# i-oboard_2.net
KiCad netlist of a schematic drawn in EAGLE
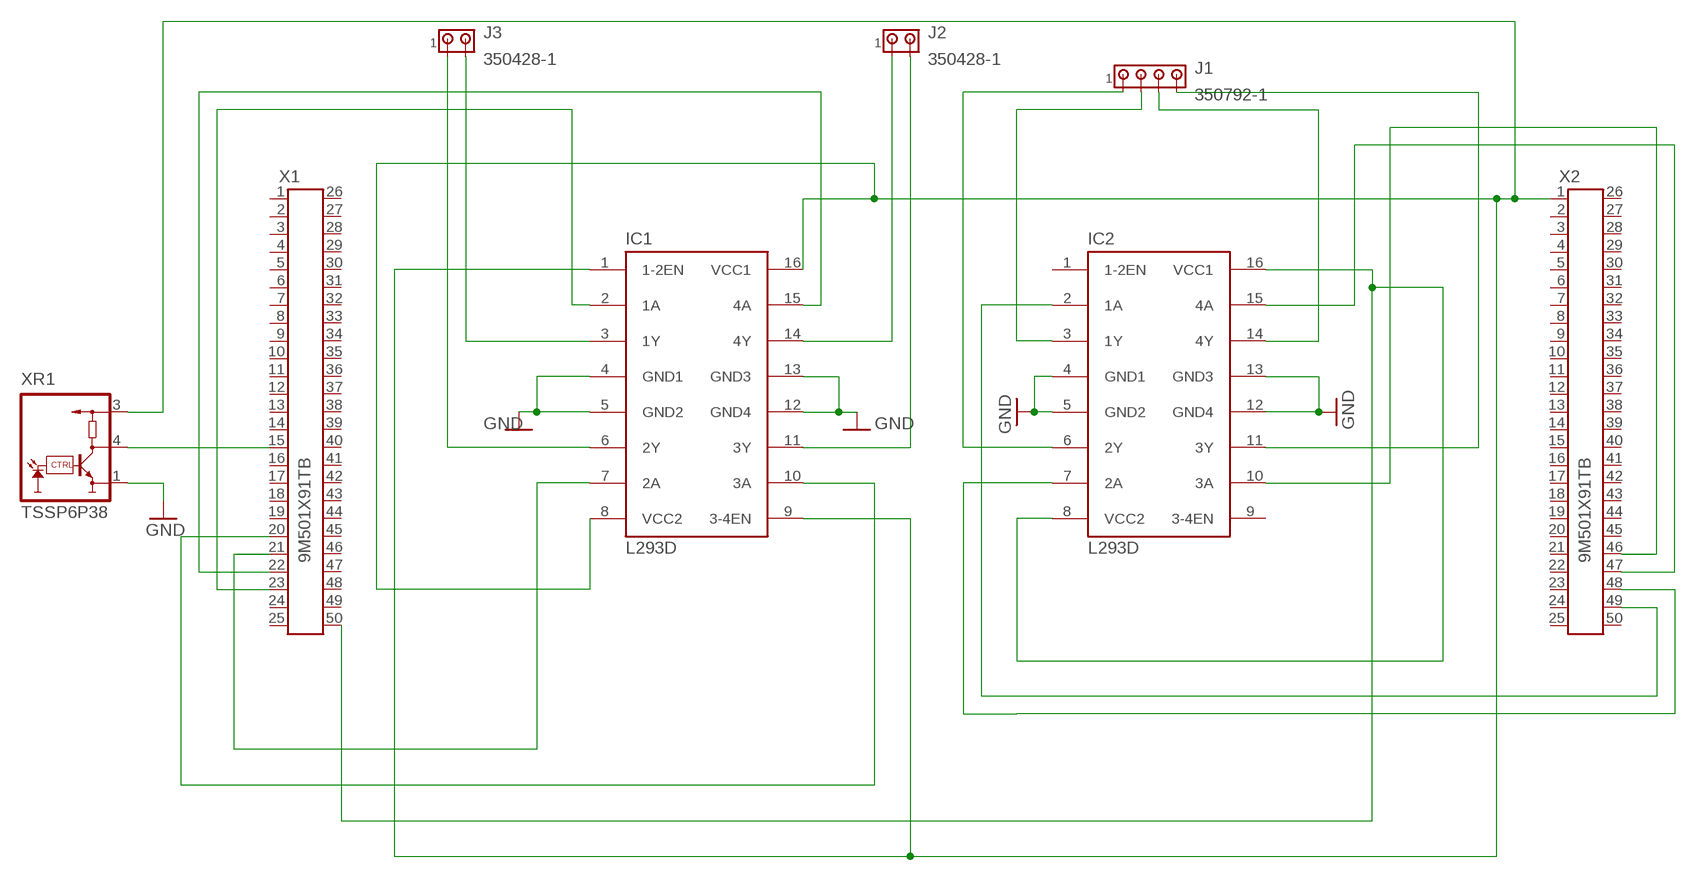
[diagram p0: schematic, sheet 1]

(export (version "E")
  (design (tool "Eeschema 10.0.6"))
  (components
    (comp (ref "IC1")
      (value "L293D")
      (footprint "eagle-import:DIL16")
      (libsource (lib "eagle-import") (part "L293D"))
    )
    (comp (ref "IC2")
      (value "L293D")
      (footprint "eagle-import:DIL16")
      (libsource (lib "eagle-import") (part "L293D"))
    )
    (comp (ref "J1")
      (value "350792-1")
      (footprint "eagle-import:350792-1")
      (libsource (lib "eagle-import") (part "350792-1"))
    )
    (comp (ref "J2")
      (value "350428-1")
      (footprint "eagle-import:350428-1")
      (libsource (lib "eagle-import") (part "350428-1"))
    )
    (comp (ref "J3")
      (value "350428-1")
      (footprint "eagle-import:350428-1")
      (libsource (lib "eagle-import") (part "350428-1"))
    )
    (comp (ref "X1")
      (value "9M501X91TB")
      (footprint "eagle-import:9M501X91")
      (libsource (lib "eagle-import") (part "9M501X91TB"))
    )
    (comp (ref "X2")
      (value "9M501X91TB")
      (footprint "eagle-import:9M501X91")
      (libsource (lib "eagle-import") (part "9M501X91TB"))
    )
    (comp (ref "XR1")
      (value "TSSP6P38")
      (footprint "eagle-import:TSSP6P38")
      (libsource (lib "eagle-import") (part "TSSP6P38"))
    )
  )
  (nets
    (net (code "1") (name "GND") (class "Default")
      (node (ref "IC1") (pin "12") (pinfunction "GND4_12") (pintype "power_in"))
      (node (ref "IC1") (pin "13") (pinfunction "GND3_13") (pintype "power_in"))
      (node (ref "IC1") (pin "4") (pinfunction "GND1_4") (pintype "power_in"))
      (node (ref "IC1") (pin "5") (pinfunction "GND2_5") (pintype "power_in"))
      (node (ref "IC2") (pin "12") (pinfunction "GND4_12") (pintype "power_in"))
      (node (ref "IC2") (pin "13") (pinfunction "GND3_13") (pintype "power_in"))
      (node (ref "IC2") (pin "4") (pinfunction "GND1_4") (pintype "power_in"))
      (node (ref "IC2") (pin "5") (pinfunction "GND2_5") (pintype "power_in"))
      (node (ref "XR1") (pin "1") (pinfunction "GND_1") (pintype "power_in"))
    )
    (net (code "2") (name "Net-(IC1-1-2EN)") (class "Default")
      (node (ref "IC1") (pin "1") (pinfunction "1-2EN_1") (pintype "input"))
      (node (ref "IC1") (pin "16") (pinfunction "VCC1_16") (pintype "power_in"))
      (node (ref "IC1") (pin "8") (pinfunction "VCC2_8") (pintype "power_in"))
      (node (ref "IC1") (pin "9") (pinfunction "3-4EN_9") (pintype "input"))
      (node (ref "X2") (pin "1") (pinfunction "1_1") (pintype "passive"))
      (node (ref "XR1") (pin "3") (pinfunction "VS_3") (pintype "power_in"))
    )
    (net (code "3") (name "Net-(IC1-1A)") (class "Default")
      (node (ref "IC1") (pin "2") (pinfunction "1A_2") (pintype "input"))
      (node (ref "X1") (pin "23") (pinfunction "23_23") (pintype "passive"))
    )
    (net (code "4") (name "Net-(IC1-1Y)") (class "Default")
      (node (ref "IC1") (pin "3") (pinfunction "1Y_3") (pintype "output"))
      (node (ref "J3") (pin "2") (pinfunction "2_2") (pintype "passive"))
    )
    (net (code "5") (name "Net-(IC1-2A)") (class "Default")
      (node (ref "IC1") (pin "7") (pinfunction "2A_7") (pintype "input"))
      (node (ref "X1") (pin "21") (pinfunction "21_21") (pintype "passive"))
    )
    (net (code "6") (name "Net-(IC1-2Y)") (class "Default")
      (node (ref "IC1") (pin "6") (pinfunction "2Y_6") (pintype "output"))
      (node (ref "J3") (pin "1") (pinfunction "1_1") (pintype "passive"))
    )
    (net (code "7") (name "Net-(IC1-3A)") (class "Default")
      (node (ref "IC1") (pin "10") (pinfunction "3A_10") (pintype "input"))
      (node (ref "X1") (pin "20") (pinfunction "20_20") (pintype "passive"))
    )
    (net (code "8") (name "Net-(IC1-3Y)") (class "Default")
      (node (ref "IC1") (pin "11") (pinfunction "3Y_11") (pintype "output"))
      (node (ref "J2") (pin "2") (pinfunction "2_2") (pintype "passive"))
    )
    (net (code "9") (name "Net-(IC1-4A)") (class "Default")
      (node (ref "IC1") (pin "15") (pinfunction "4A_15") (pintype "input"))
      (node (ref "X1") (pin "22") (pinfunction "22_22") (pintype "passive"))
    )
    (net (code "10") (name "Net-(IC1-4Y)") (class "Default")
      (node (ref "IC1") (pin "14") (pinfunction "4Y_14") (pintype "output"))
      (node (ref "J2") (pin "1") (pinfunction "1_1") (pintype "passive"))
    )
    (net (code "11") (name "Net-(IC2-1A)") (class "Default")
      (node (ref "IC2") (pin "2") (pinfunction "1A_2") (pintype "input"))
      (node (ref "X2") (pin "49") (pinfunction "49_49") (pintype "passive"))
    )
    (net (code "12") (name "Net-(IC2-1Y)") (class "Default")
      (node (ref "IC2") (pin "3") (pinfunction "1Y_3") (pintype "output"))
      (node (ref "J1") (pin "2") (pinfunction "2_2") (pintype "passive"))
    )
    (net (code "13") (name "Net-(IC2-2A)") (class "Default")
      (node (ref "IC2") (pin "7") (pinfunction "2A_7") (pintype "input"))
      (node (ref "X2") (pin "48") (pinfunction "48_48") (pintype "passive"))
    )
    (net (code "14") (name "Net-(IC2-2Y)") (class "Default")
      (node (ref "IC2") (pin "6") (pinfunction "2Y_6") (pintype "output"))
      (node (ref "J1") (pin "1") (pinfunction "1_1") (pintype "passive"))
    )
    (net (code "15") (name "Net-(IC2-3A)") (class "Default")
      (node (ref "IC2") (pin "10") (pinfunction "3A_10") (pintype "input"))
      (node (ref "X2") (pin "46") (pinfunction "46_46") (pintype "passive"))
    )
    (net (code "16") (name "Net-(IC2-3Y)") (class "Default")
      (node (ref "IC2") (pin "11") (pinfunction "3Y_11") (pintype "output"))
      (node (ref "J1") (pin "4") (pinfunction "4_4") (pintype "passive"))
    )
    (net (code "17") (name "Net-(IC2-4A)") (class "Default")
      (node (ref "IC2") (pin "15") (pinfunction "4A_15") (pintype "input"))
      (node (ref "X2") (pin "47") (pinfunction "47_47") (pintype "passive"))
    )
    (net (code "18") (name "Net-(IC2-4Y)") (class "Default")
      (node (ref "IC2") (pin "14") (pinfunction "4Y_14") (pintype "output"))
      (node (ref "J1") (pin "3") (pinfunction "3_3") (pintype "passive"))
    )
    (net (code "19") (name "Net-(IC2-VCC1)") (class "Default")
      (node (ref "IC2") (pin "16") (pinfunction "VCC1_16") (pintype "power_in"))
      (node (ref "IC2") (pin "8") (pinfunction "VCC2_8") (pintype "power_in"))
      (node (ref "X1") (pin "50") (pinfunction "50_50") (pintype "passive"))
    )
    (net (code "20") (name "Net-(XR1-OUT)") (class "Default")
      (node (ref "X1") (pin "15") (pinfunction "15_15") (pintype "passive"))
      (node (ref "XR1") (pin "4") (pinfunction "OUT_4") (pintype "output"))
    )
    (net (code "21") (name "unconnected-(IC2-1-2EN-Pad1)") (class "Default")
      (node (ref "IC2") (pin "1") (pinfunction "1-2EN_1") (pintype "input"))
    )
    (net (code "22") (name "unconnected-(IC2-3-4EN-Pad9)") (class "Default")
      (node (ref "IC2") (pin "9") (pinfunction "3-4EN_9") (pintype "input"))
    )
    (net (code "23") (name "unconnected-(X1-Pad1)") (class "Default")
      (node (ref "X1") (pin "1") (pinfunction "1_1") (pintype "passive"))
    )
    (net (code "24") (name "unconnected-(X1-Pad2)") (class "Default")
      (node (ref "X1") (pin "2") (pinfunction "2_2") (pintype "passive"))
    )
    (net (code "25") (name "unconnected-(X1-Pad3)") (class "Default")
      (node (ref "X1") (pin "3") (pinfunction "3_3") (pintype "passive"))
    )
    (net (code "26") (name "unconnected-(X1-Pad4)") (class "Default")
      (node (ref "X1") (pin "4") (pinfunction "4_4") (pintype "passive"))
    )
    (net (code "27") (name "unconnected-(X1-Pad5)") (class "Default")
      (node (ref "X1") (pin "5") (pinfunction "5_5") (pintype "passive"))
    )
    (net (code "28") (name "unconnected-(X1-Pad6)") (class "Default")
      (node (ref "X1") (pin "6") (pinfunction "6_6") (pintype "passive"))
    )
    (net (code "29") (name "unconnected-(X1-Pad7)") (class "Default")
      (node (ref "X1") (pin "7") (pinfunction "7_7") (pintype "passive"))
    )
    (net (code "30") (name "unconnected-(X1-Pad8)") (class "Default")
      (node (ref "X1") (pin "8") (pinfunction "8_8") (pintype "passive"))
    )
    (net (code "31") (name "unconnected-(X1-Pad9)") (class "Default")
      (node (ref "X1") (pin "9") (pinfunction "9_9") (pintype "passive"))
    )
    (net (code "32") (name "unconnected-(X1-Pad10)") (class "Default")
      (node (ref "X1") (pin "10") (pinfunction "10_10") (pintype "passive"))
    )
    (net (code "33") (name "unconnected-(X1-Pad11)") (class "Default")
      (node (ref "X1") (pin "11") (pinfunction "11_11") (pintype "passive"))
    )
    (net (code "34") (name "unconnected-(X1-Pad12)") (class "Default")
      (node (ref "X1") (pin "12") (pinfunction "12_12") (pintype "passive"))
    )
    (net (code "35") (name "unconnected-(X1-Pad13)") (class "Default")
      (node (ref "X1") (pin "13") (pinfunction "13_13") (pintype "passive"))
    )
    (net (code "36") (name "unconnected-(X1-Pad14)") (class "Default")
      (node (ref "X1") (pin "14") (pinfunction "14_14") (pintype "passive"))
    )
    (net (code "37") (name "unconnected-(X1-Pad16)") (class "Default")
      (node (ref "X1") (pin "16") (pinfunction "16_16") (pintype "passive"))
    )
    (net (code "38") (name "unconnected-(X1-Pad17)") (class "Default")
      (node (ref "X1") (pin "17") (pinfunction "17_17") (pintype "passive"))
    )
    (net (code "39") (name "unconnected-(X1-Pad18)") (class "Default")
      (node (ref "X1") (pin "18") (pinfunction "18_18") (pintype "passive"))
    )
    (net (code "40") (name "unconnected-(X1-Pad19)") (class "Default")
      (node (ref "X1") (pin "19") (pinfunction "19_19") (pintype "passive"))
    )
    (net (code "41") (name "unconnected-(X1-Pad24)") (class "Default")
      (node (ref "X1") (pin "24") (pinfunction "24_24") (pintype "passive"))
    )
    (net (code "42") (name "unconnected-(X1-Pad25)") (class "Default")
      (node (ref "X1") (pin "25") (pinfunction "25_25") (pintype "passive"))
    )
    (net (code "43") (name "unconnected-(X1-Pad26)") (class "Default")
      (node (ref "X1") (pin "26") (pinfunction "26_26") (pintype "passive"))
    )
    (net (code "44") (name "unconnected-(X1-Pad27)") (class "Default")
      (node (ref "X1") (pin "27") (pinfunction "27_27") (pintype "passive"))
    )
    (net (code "45") (name "unconnected-(X1-Pad28)") (class "Default")
      (node (ref "X1") (pin "28") (pinfunction "28_28") (pintype "passive"))
    )
    (net (code "46") (name "unconnected-(X1-Pad29)") (class "Default")
      (node (ref "X1") (pin "29") (pinfunction "29_29") (pintype "passive"))
    )
    (net (code "47") (name "unconnected-(X1-Pad30)") (class "Default")
      (node (ref "X1") (pin "30") (pinfunction "30_30") (pintype "passive"))
    )
    (net (code "48") (name "unconnected-(X1-Pad31)") (class "Default")
      (node (ref "X1") (pin "31") (pinfunction "31_31") (pintype "passive"))
    )
    (net (code "49") (name "unconnected-(X1-Pad32)") (class "Default")
      (node (ref "X1") (pin "32") (pinfunction "32_32") (pintype "passive"))
    )
    (net (code "50") (name "unconnected-(X1-Pad33)") (class "Default")
      (node (ref "X1") (pin "33") (pinfunction "33_33") (pintype "passive"))
    )
    (net (code "51") (name "unconnected-(X1-Pad34)") (class "Default")
      (node (ref "X1") (pin "34") (pinfunction "34_34") (pintype "passive"))
    )
    (net (code "52") (name "unconnected-(X1-Pad35)") (class "Default")
      (node (ref "X1") (pin "35") (pinfunction "35_35") (pintype "passive"))
    )
    (net (code "53") (name "unconnected-(X1-Pad36)") (class "Default")
      (node (ref "X1") (pin "36") (pinfunction "36_36") (pintype "passive"))
    )
    (net (code "54") (name "unconnected-(X1-Pad37)") (class "Default")
      (node (ref "X1") (pin "37") (pinfunction "37_37") (pintype "passive"))
    )
    (net (code "55") (name "unconnected-(X1-Pad38)") (class "Default")
      (node (ref "X1") (pin "38") (pinfunction "38_38") (pintype "passive"))
    )
    (net (code "56") (name "unconnected-(X1-Pad39)") (class "Default")
      (node (ref "X1") (pin "39") (pinfunction "39_39") (pintype "passive"))
    )
    (net (code "57") (name "unconnected-(X1-Pad40)") (class "Default")
      (node (ref "X1") (pin "40") (pinfunction "40_40") (pintype "passive"))
    )
    (net (code "58") (name "unconnected-(X1-Pad41)") (class "Default")
      (node (ref "X1") (pin "41") (pinfunction "41_41") (pintype "passive"))
    )
    (net (code "59") (name "unconnected-(X1-Pad42)") (class "Default")
      (node (ref "X1") (pin "42") (pinfunction "42_42") (pintype "passive"))
    )
    (net (code "60") (name "unconnected-(X1-Pad43)") (class "Default")
      (node (ref "X1") (pin "43") (pinfunction "43_43") (pintype "passive"))
    )
    (net (code "61") (name "unconnected-(X1-Pad44)") (class "Default")
      (node (ref "X1") (pin "44") (pinfunction "44_44") (pintype "passive"))
    )
    (net (code "62") (name "unconnected-(X1-Pad45)") (class "Default")
      (node (ref "X1") (pin "45") (pinfunction "45_45") (pintype "passive"))
    )
    (net (code "63") (name "unconnected-(X1-Pad46)") (class "Default")
      (node (ref "X1") (pin "46") (pinfunction "46_46") (pintype "passive"))
    )
    (net (code "64") (name "unconnected-(X1-Pad47)") (class "Default")
      (node (ref "X1") (pin "47") (pinfunction "47_47") (pintype "passive"))
    )
    (net (code "65") (name "unconnected-(X1-Pad48)") (class "Default")
      (node (ref "X1") (pin "48") (pinfunction "48_48") (pintype "passive"))
    )
    (net (code "66") (name "unconnected-(X1-Pad49)") (class "Default")
      (node (ref "X1") (pin "49") (pinfunction "49_49") (pintype "passive"))
    )
    (net (code "67") (name "unconnected-(X2-Pad2)") (class "Default")
      (node (ref "X2") (pin "2") (pinfunction "2_2") (pintype "passive"))
    )
    (net (code "68") (name "unconnected-(X2-Pad3)") (class "Default")
      (node (ref "X2") (pin "3") (pinfunction "3_3") (pintype "passive"))
    )
    (net (code "69") (name "unconnected-(X2-Pad4)") (class "Default")
      (node (ref "X2") (pin "4") (pinfunction "4_4") (pintype "passive"))
    )
    (net (code "70") (name "unconnected-(X2-Pad5)") (class "Default")
      (node (ref "X2") (pin "5") (pinfunction "5_5") (pintype "passive"))
    )
    (net (code "71") (name "unconnected-(X2-Pad6)") (class "Default")
      (node (ref "X2") (pin "6") (pinfunction "6_6") (pintype "passive"))
    )
    (net (code "72") (name "unconnected-(X2-Pad7)") (class "Default")
      (node (ref "X2") (pin "7") (pinfunction "7_7") (pintype "passive"))
    )
    (net (code "73") (name "unconnected-(X2-Pad8)") (class "Default")
      (node (ref "X2") (pin "8") (pinfunction "8_8") (pintype "passive"))
    )
    (net (code "74") (name "unconnected-(X2-Pad9)") (class "Default")
      (node (ref "X2") (pin "9") (pinfunction "9_9") (pintype "passive"))
    )
    (net (code "75") (name "unconnected-(X2-Pad10)") (class "Default")
      (node (ref "X2") (pin "10") (pinfunction "10_10") (pintype "passive"))
    )
    (net (code "76") (name "unconnected-(X2-Pad11)") (class "Default")
      (node (ref "X2") (pin "11") (pinfunction "11_11") (pintype "passive"))
    )
    (net (code "77") (name "unconnected-(X2-Pad12)") (class "Default")
      (node (ref "X2") (pin "12") (pinfunction "12_12") (pintype "passive"))
    )
    (net (code "78") (name "unconnected-(X2-Pad13)") (class "Default")
      (node (ref "X2") (pin "13") (pinfunction "13_13") (pintype "passive"))
    )
    (net (code "79") (name "unconnected-(X2-Pad14)") (class "Default")
      (node (ref "X2") (pin "14") (pinfunction "14_14") (pintype "passive"))
    )
    (net (code "80") (name "unconnected-(X2-Pad15)") (class "Default")
      (node (ref "X2") (pin "15") (pinfunction "15_15") (pintype "passive"))
    )
    (net (code "81") (name "unconnected-(X2-Pad16)") (class "Default")
      (node (ref "X2") (pin "16") (pinfunction "16_16") (pintype "passive"))
    )
    (net (code "82") (name "unconnected-(X2-Pad17)") (class "Default")
      (node (ref "X2") (pin "17") (pinfunction "17_17") (pintype "passive"))
    )
    (net (code "83") (name "unconnected-(X2-Pad18)") (class "Default")
      (node (ref "X2") (pin "18") (pinfunction "18_18") (pintype "passive"))
    )
    (net (code "84") (name "unconnected-(X2-Pad19)") (class "Default")
      (node (ref "X2") (pin "19") (pinfunction "19_19") (pintype "passive"))
    )
    (net (code "85") (name "unconnected-(X2-Pad20)") (class "Default")
      (node (ref "X2") (pin "20") (pinfunction "20_20") (pintype "passive"))
    )
    (net (code "86") (name "unconnected-(X2-Pad21)") (class "Default")
      (node (ref "X2") (pin "21") (pinfunction "21_21") (pintype "passive"))
    )
    (net (code "87") (name "unconnected-(X2-Pad22)") (class "Default")
      (node (ref "X2") (pin "22") (pinfunction "22_22") (pintype "passive"))
    )
    (net (code "88") (name "unconnected-(X2-Pad23)") (class "Default")
      (node (ref "X2") (pin "23") (pinfunction "23_23") (pintype "passive"))
    )
    (net (code "89") (name "unconnected-(X2-Pad24)") (class "Default")
      (node (ref "X2") (pin "24") (pinfunction "24_24") (pintype "passive"))
    )
    (net (code "90") (name "unconnected-(X2-Pad25)") (class "Default")
      (node (ref "X2") (pin "25") (pinfunction "25_25") (pintype "passive"))
    )
    (net (code "91") (name "unconnected-(X2-Pad26)") (class "Default")
      (node (ref "X2") (pin "26") (pinfunction "26_26") (pintype "passive"))
    )
    (net (code "92") (name "unconnected-(X2-Pad27)") (class "Default")
      (node (ref "X2") (pin "27") (pinfunction "27_27") (pintype "passive"))
    )
    (net (code "93") (name "unconnected-(X2-Pad28)") (class "Default")
      (node (ref "X2") (pin "28") (pinfunction "28_28") (pintype "passive"))
    )
    (net (code "94") (name "unconnected-(X2-Pad29)") (class "Default")
      (node (ref "X2") (pin "29") (pinfunction "29_29") (pintype "passive"))
    )
    (net (code "95") (name "unconnected-(X2-Pad30)") (class "Default")
      (node (ref "X2") (pin "30") (pinfunction "30_30") (pintype "passive"))
    )
    (net (code "96") (name "unconnected-(X2-Pad31)") (class "Default")
      (node (ref "X2") (pin "31") (pinfunction "31_31") (pintype "passive"))
    )
    (net (code "97") (name "unconnected-(X2-Pad32)") (class "Default")
      (node (ref "X2") (pin "32") (pinfunction "32_32") (pintype "passive"))
    )
    (net (code "98") (name "unconnected-(X2-Pad33)") (class "Default")
      (node (ref "X2") (pin "33") (pinfunction "33_33") (pintype "passive"))
    )
    (net (code "99") (name "unconnected-(X2-Pad34)") (class "Default")
      (node (ref "X2") (pin "34") (pinfunction "34_34") (pintype "passive"))
    )
    (net (code "100") (name "unconnected-(X2-Pad35)") (class "Default")
      (node (ref "X2") (pin "35") (pinfunction "35_35") (pintype "passive"))
    )
    (net (code "101") (name "unconnected-(X2-Pad36)") (class "Default")
      (node (ref "X2") (pin "36") (pinfunction "36_36") (pintype "passive"))
    )
    (net (code "102") (name "unconnected-(X2-Pad37)") (class "Default")
      (node (ref "X2") (pin "37") (pinfunction "37_37") (pintype "passive"))
    )
    (net (code "103") (name "unconnected-(X2-Pad38)") (class "Default")
      (node (ref "X2") (pin "38") (pinfunction "38_38") (pintype "passive"))
    )
    (net (code "104") (name "unconnected-(X2-Pad39)") (class "Default")
      (node (ref "X2") (pin "39") (pinfunction "39_39") (pintype "passive"))
    )
    (net (code "105") (name "unconnected-(X2-Pad40)") (class "Default")
      (node (ref "X2") (pin "40") (pinfunction "40_40") (pintype "passive"))
    )
    (net (code "106") (name "unconnected-(X2-Pad41)") (class "Default")
      (node (ref "X2") (pin "41") (pinfunction "41_41") (pintype "passive"))
    )
    (net (code "107") (name "unconnected-(X2-Pad42)") (class "Default")
      (node (ref "X2") (pin "42") (pinfunction "42_42") (pintype "passive"))
    )
    (net (code "108") (name "unconnected-(X2-Pad43)") (class "Default")
      (node (ref "X2") (pin "43") (pinfunction "43_43") (pintype "passive"))
    )
    (net (code "109") (name "unconnected-(X2-Pad44)") (class "Default")
      (node (ref "X2") (pin "44") (pinfunction "44_44") (pintype "passive"))
    )
    (net (code "110") (name "unconnected-(X2-Pad45)") (class "Default")
      (node (ref "X2") (pin "45") (pinfunction "45_45") (pintype "passive"))
    )
    (net (code "111") (name "unconnected-(X2-Pad50)") (class "Default")
      (node (ref "X2") (pin "50") (pinfunction "50_50") (pintype "passive"))
    )
  )
)
